# circuit.net
KiCad netlist of a schematic drawn in EAGLE
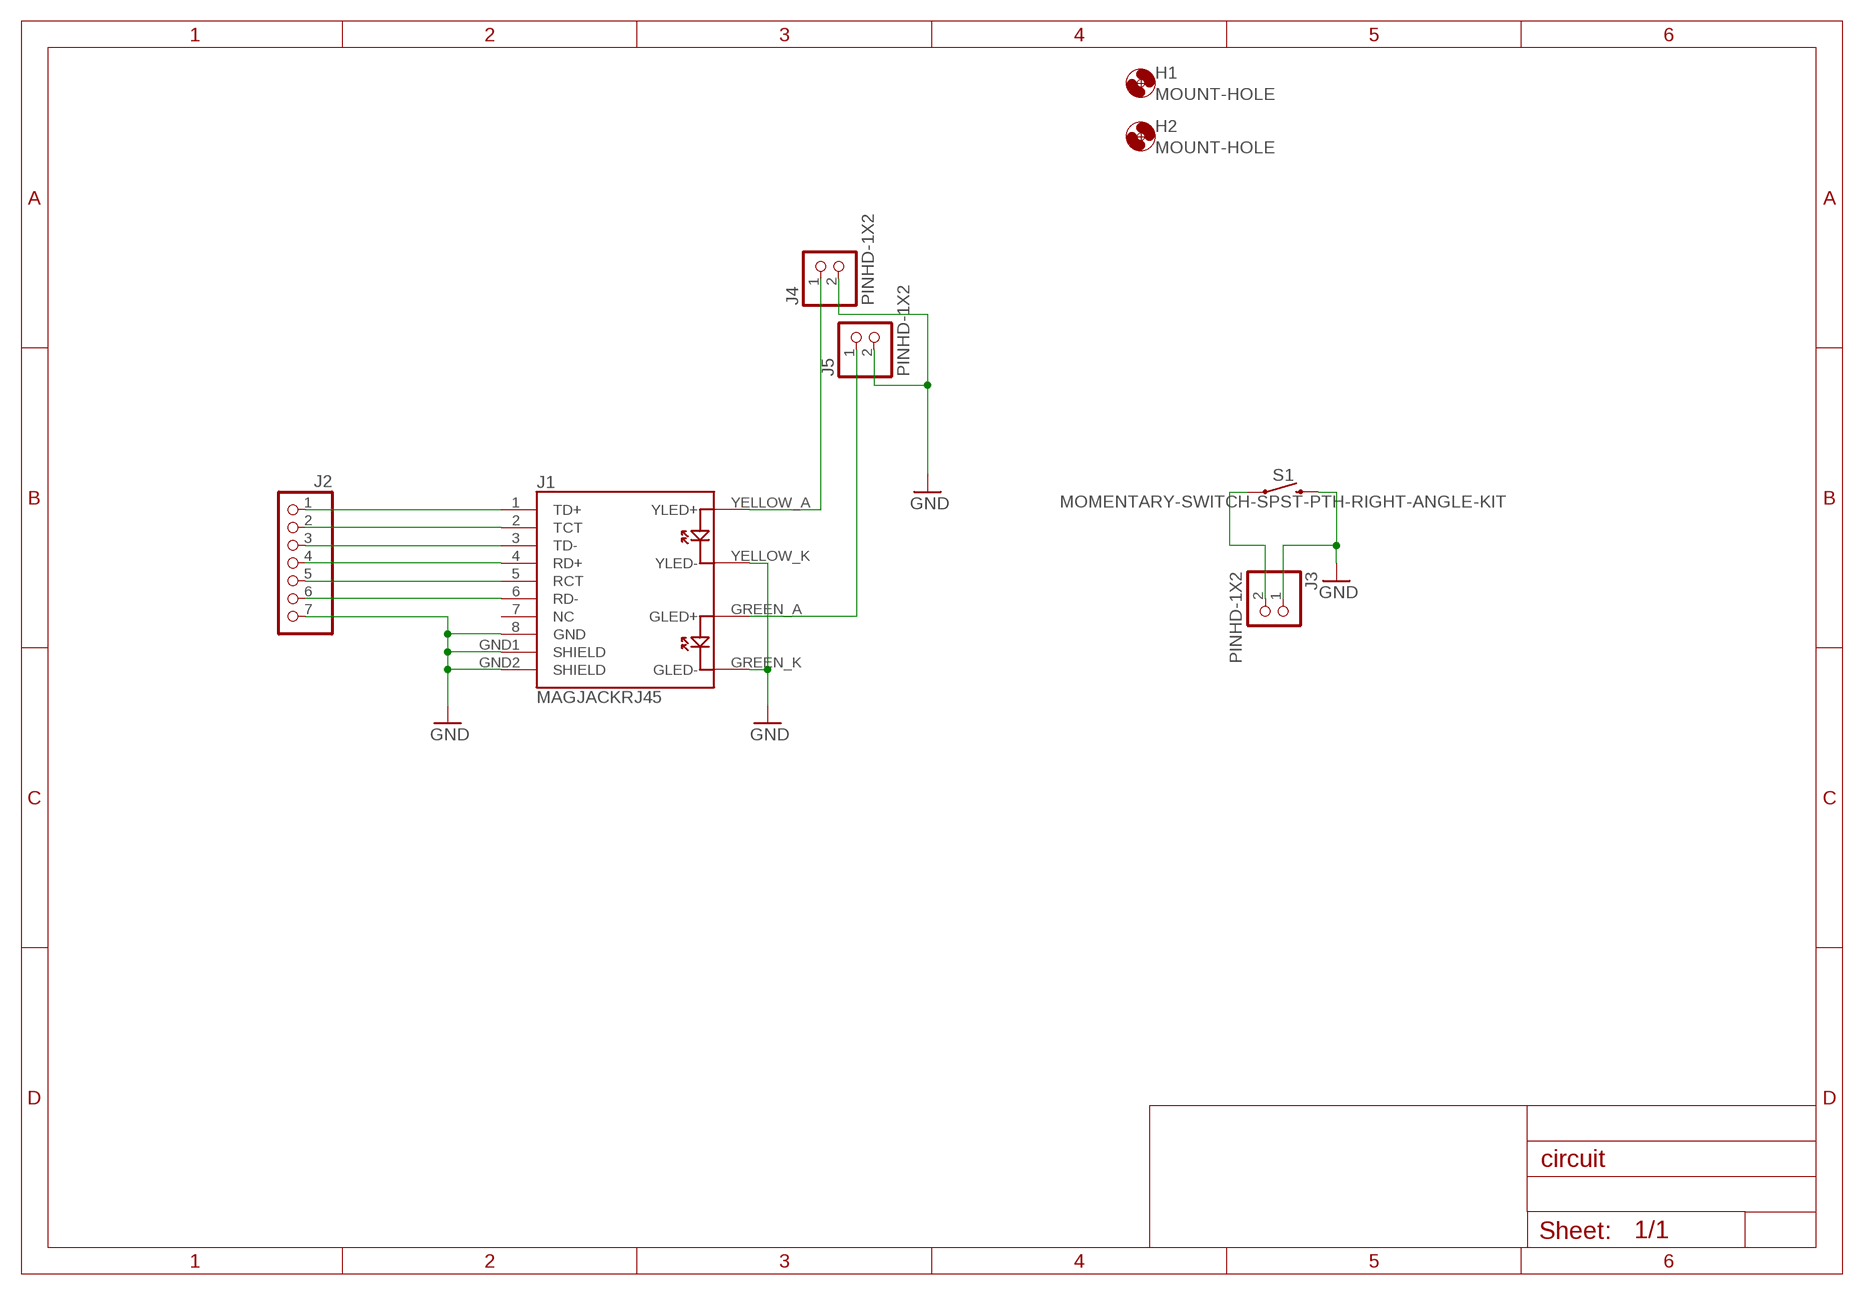
[diagram p0: schematic, sheet 1]

(export (version "E")
  (design (tool "Eeschema 10.0.6"))
  (components
    (comp (ref "H1")
      (value "MOUNT-HOLE")
      (footprint "eagle-import:3,2")
      (libsource (lib "eagle-import") (part "MOUNT-HOLE"))
    )
    (comp (ref "H2")
      (value "MOUNT-HOLE")
      (footprint "eagle-import:3,2")
      (libsource (lib "eagle-import") (part "MOUNT-HOLE"))
    )
    (comp (ref "J1")
      (value "MAGJACKRJ45")
      (footprint "eagle-import:MAGJACK")
      (libsource (lib "eagle-import") (part "MAGJACKRJ45"))
    )
    (comp (ref "J2")
      (value "PINHD-1X7")
      (footprint "eagle-import:1X07")
      (libsource (lib "eagle-import") (part "PINHD-1X7"))
    )
    (comp (ref "J3")
      (value "PINHD-1X2")
      (footprint "eagle-import:1X02")
      (libsource (lib "eagle-import") (part "PINHD-1X2"))
    )
    (comp (ref "J4")
      (value "PINHD-1X2")
      (footprint "eagle-import:1X02")
      (libsource (lib "eagle-import") (part "PINHD-1X2"))
    )
    (comp (ref "J5")
      (value "PINHD-1X2")
      (footprint "eagle-import:1X02")
      (libsource (lib "eagle-import") (part "PINHD-1X2"))
    )
    (comp (ref "S1")
      (value "MOMENTARY-SWITCH-SPST-PTH-RIGHT-ANGLE-KIT")
      (footprint "eagle-import:TACTILE_SWITCH_PTH_RIGHT_ANGLE_KIT")
      (libsource (lib "eagle-import") (part "MOMENTARY-SWITCH-SPST-PTH-RIGHT-ANGLE-KIT"))
    )
  )
  (nets
    (net (code "1") (name "GND") (class "Default")
      (node (ref "J1") (pin "8") (pinfunction "GND_8") (pintype "bidirectional"))
      (node (ref "J1") (pin "GND1") (pinfunction "SHIELD_GND1") (pintype "bidirectional"))
      (node (ref "J1") (pin "GND2") (pinfunction "SHIELD_GND2") (pintype "bidirectional"))
      (node (ref "J1") (pin "GREEN_K") (pinfunction "GLED-_GREEN_K") (pintype "bidirectional"))
      (node (ref "J1") (pin "YELLOW_K") (pinfunction "YLED-_YELLOW_K") (pintype "bidirectional"))
      (node (ref "J2") (pin "7") (pinfunction "7_7") (pintype "passive"))
      (node (ref "J3") (pin "1") (pinfunction "1_1") (pintype "passive"))
      (node (ref "J4") (pin "2") (pinfunction "2_2") (pintype "passive"))
      (node (ref "J5") (pin "2") (pinfunction "2_2") (pintype "passive"))
      (node (ref "S1") (pin "2") (pinfunction "2_2") (pintype "passive"))
    )
    (net (code "2") (name "Net-(J1-GLED+)") (class "Default")
      (node (ref "J1") (pin "GREEN_A") (pinfunction "GLED+_GREEN_A") (pintype "bidirectional"))
      (node (ref "J5") (pin "1") (pinfunction "1_1") (pintype "passive"))
    )
    (net (code "3") (name "Net-(J1-RCT)") (class "Default")
      (node (ref "J1") (pin "5") (pinfunction "RCT_5") (pintype "bidirectional"))
      (node (ref "J2") (pin "5") (pinfunction "5_5") (pintype "passive"))
    )
    (net (code "4") (name "Net-(J1-RD+)") (class "Default")
      (node (ref "J1") (pin "4") (pinfunction "RD+_4") (pintype "bidirectional"))
      (node (ref "J2") (pin "4") (pinfunction "4_4") (pintype "passive"))
    )
    (net (code "5") (name "Net-(J1-RD-)") (class "Default")
      (node (ref "J1") (pin "6") (pinfunction "RD-_6") (pintype "bidirectional"))
      (node (ref "J2") (pin "6") (pinfunction "6_6") (pintype "passive"))
    )
    (net (code "6") (name "Net-(J1-TCT)") (class "Default")
      (node (ref "J1") (pin "2") (pinfunction "TCT_2") (pintype "bidirectional"))
      (node (ref "J2") (pin "2") (pinfunction "2_2") (pintype "passive"))
    )
    (net (code "7") (name "Net-(J1-TD+)") (class "Default")
      (node (ref "J1") (pin "1") (pinfunction "TD+_1") (pintype "bidirectional"))
      (node (ref "J2") (pin "1") (pinfunction "1_1") (pintype "passive"))
    )
    (net (code "8") (name "Net-(J1-TD-)") (class "Default")
      (node (ref "J1") (pin "3") (pinfunction "TD-_3") (pintype "bidirectional"))
      (node (ref "J2") (pin "3") (pinfunction "3_3") (pintype "passive"))
    )
    (net (code "9") (name "Net-(J1-YLED+)") (class "Default")
      (node (ref "J1") (pin "YELLOW_A") (pinfunction "YLED+_YELLOW_A") (pintype "bidirectional"))
      (node (ref "J4") (pin "1") (pinfunction "1_1") (pintype "passive"))
    )
    (net (code "10") (name "Net-(J3-Pad2)") (class "Default")
      (node (ref "J3") (pin "2") (pinfunction "2_2") (pintype "passive"))
      (node (ref "S1") (pin "1") (pinfunction "1_1") (pintype "passive"))
    )
    (net (code "11") (name "unconnected-(J1-NC-Pad7)") (class "Default")
      (node (ref "J1") (pin "7") (pinfunction "NC_7") (pintype "bidirectional"))
    )
  )
)
